# OutputAmplifier.net
KiCad netlist of a schematic drawn in Altium Designer
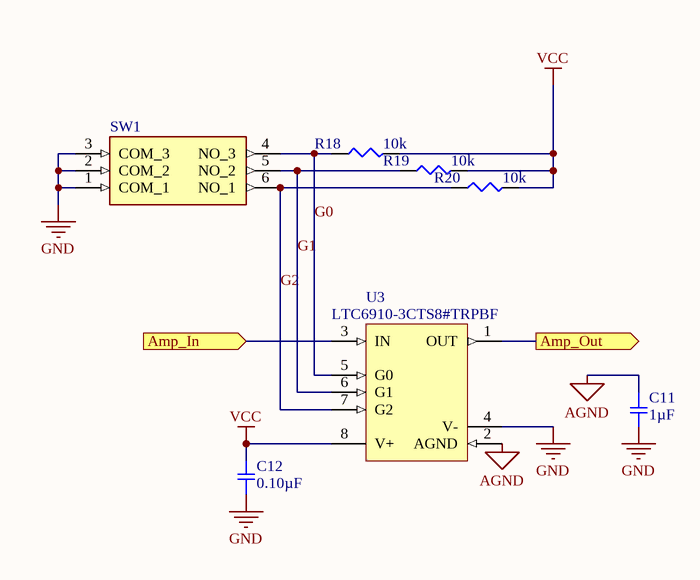
[diagram p0: OutputAmplifier.SchDoc]

(export (version "E")
  (design (tool "Eeschema 10.0.6"))
  (components
    (comp (ref "C11")
      (value "1µF")
      (footprint "SMD-0603C")
      (description "CAP CER 1UF 16V X7R 0603")
      (fields
        (field (name "DIGI-KEY PART NUMBER") "490-5241-1-ND")
        (field (name "PART NUMBER") "GCM188R71C105KA64D")
      )
      (libsource (lib "capacitor_murata_0603") (part "GCM188R71C105KA64D"))
    )
    (comp (ref "C12")
      (value "0.10µF")
      (footprint "SMD-0603C")
      (description "CAP CER 0.1UF 16V X7R 0603")
      (fields
        (field (name "DIGI-KEY PART NUMBER") "490-5796-1-ND")
        (field (name "PART NUMBER") "GCJ188R71C104KA01D")
      )
      (libsource (lib "capacitor_murata_0603") (part "GCJ188R71C104KA01D"))
    )
    (comp (ref "R18")
      (value "10k")
      (footprint "SMD-0603-RES")
      (description "RES SMD 10K OHM 1% 1/10W 0603")
      (fields
        (field (name "MANUFACTURER") "Panasonic Electronic Components")
        (field (name "MANUFACTURER PART NUMBER") "RNCP0603FTD10K0")
      )
      (libsource (lib "Panasonic_resistor_0603") (part "ERJ-3EKF1002V"))
    )
    (comp (ref "R19")
      (value "10k")
      (footprint "SMD-0603-RES")
      (description "RES SMD 10K OHM 1% 1/10W 0603")
      (fields
        (field (name "MANUFACTURER") "Panasonic Electronic Components")
        (field (name "MANUFACTURER PART NUMBER") "RNCP0603FTD10K0")
      )
      (libsource (lib "Panasonic_resistor_0603") (part "ERJ-3EKF1002V"))
    )
    (comp (ref "R20")
      (value "10k")
      (footprint "SMD-0603-RES")
      (description "RES SMD 10K OHM 1% 1/10W 0603")
      (fields
        (field (name "MANUFACTURER") "Panasonic Electronic Components")
        (field (name "MANUFACTURER PART NUMBER") "RNCP0603FTD10K0")
      )
      (libsource (lib "Panasonic_resistor_0603") (part "ERJ-3EKF1002V"))
    )
    (comp (ref "SW1")
      (value "416131160803")
      (footprint "416131160803")
      (description "Switch")
      (fields (field (name "MOUSER PART NUMBER") "710-416131160803"))
      (libsource (lib "URC_Lib") (part "416131160803"))
    )
    (comp (ref "U3")
      (value "LTC6910-3CTS8#TRPBF")
      (footprint "LT-TS8-8-TSOT-23_V")
      (fields
        (field (name "MANUFACTURER") "Analog Devices Inc.")
        (field (name "MANUFACTURER PART NUMBER") "LTC6910-3CTS8#TRMPBF")
      )
      (libsource (lib "Altium Content Vault") (part "LT-LTC6910-TS8-8"))
    )
  )
  (nets
    (net (code "1") (name "/Amp_In") (class "Default")
      (node (ref "U3") (pin "3") (pinfunction "IN_3") (pintype "input"))
    )
    (net (code "2") (name "/Amp_Out") (class "Default")
      (node (ref "U3") (pin "1") (pinfunction "OUT_1") (pintype "output"))
    )
    (net (code "3") (name "/G0") (class "Default")
      (node (ref "R18") (pin "1") (pinfunction "1_1") (pintype "passive"))
      (node (ref "SW1") (pin "4") (pinfunction "NO_3_4") (pintype "output"))
      (node (ref "U3") (pin "5") (pinfunction "G0_5") (pintype "input"))
    )
    (net (code "4") (name "/G1") (class "Default")
      (node (ref "R19") (pin "1") (pinfunction "1_1") (pintype "passive"))
      (node (ref "SW1") (pin "5") (pinfunction "NO_2_5") (pintype "output"))
      (node (ref "U3") (pin "6") (pinfunction "G1_6") (pintype "input"))
    )
    (net (code "5") (name "/G2") (class "Default")
      (node (ref "R20") (pin "1") (pinfunction "1_1") (pintype "passive"))
      (node (ref "SW1") (pin "6") (pinfunction "NO_1_6") (pintype "output"))
      (node (ref "U3") (pin "7") (pinfunction "G2_7") (pintype "input"))
    )
    (net (code "6") (name "AGND") (class "Default")
      (node (ref "C11") (pin "1") (pinfunction "1_1") (pintype "passive"))
      (node (ref "U3") (pin "2") (pinfunction "AGND_2") (pintype "input"))
    )
    (net (code "7") (name "GND") (class "Default")
      (node (ref "C11") (pin "2") (pinfunction "2_2") (pintype "passive"))
      (node (ref "C12") (pin "1") (pinfunction "1_1") (pintype "passive"))
      (node (ref "SW1") (pin "1") (pinfunction "COM_1_1") (pintype "input"))
      (node (ref "SW1") (pin "2") (pinfunction "COM_2_2") (pintype "input"))
      (node (ref "SW1") (pin "3") (pinfunction "COM_3_3") (pintype "input"))
      (node (ref "U3") (pin "4") (pinfunction "V-_4") (pintype "power_in"))
    )
    (net (code "8") (name "VCC") (class "Default")
      (node (ref "C12") (pin "2") (pinfunction "2_2") (pintype "passive"))
      (node (ref "R18") (pin "2") (pinfunction "2_2") (pintype "passive"))
      (node (ref "R19") (pin "2") (pinfunction "2_2") (pintype "passive"))
      (node (ref "R20") (pin "2") (pinfunction "2_2") (pintype "passive"))
      (node (ref "U3") (pin "8") (pinfunction "V+_8") (pintype "power_in"))
    )
  )
)
